# working.net
KiCad netlist of a schematic drawn in EAGLE
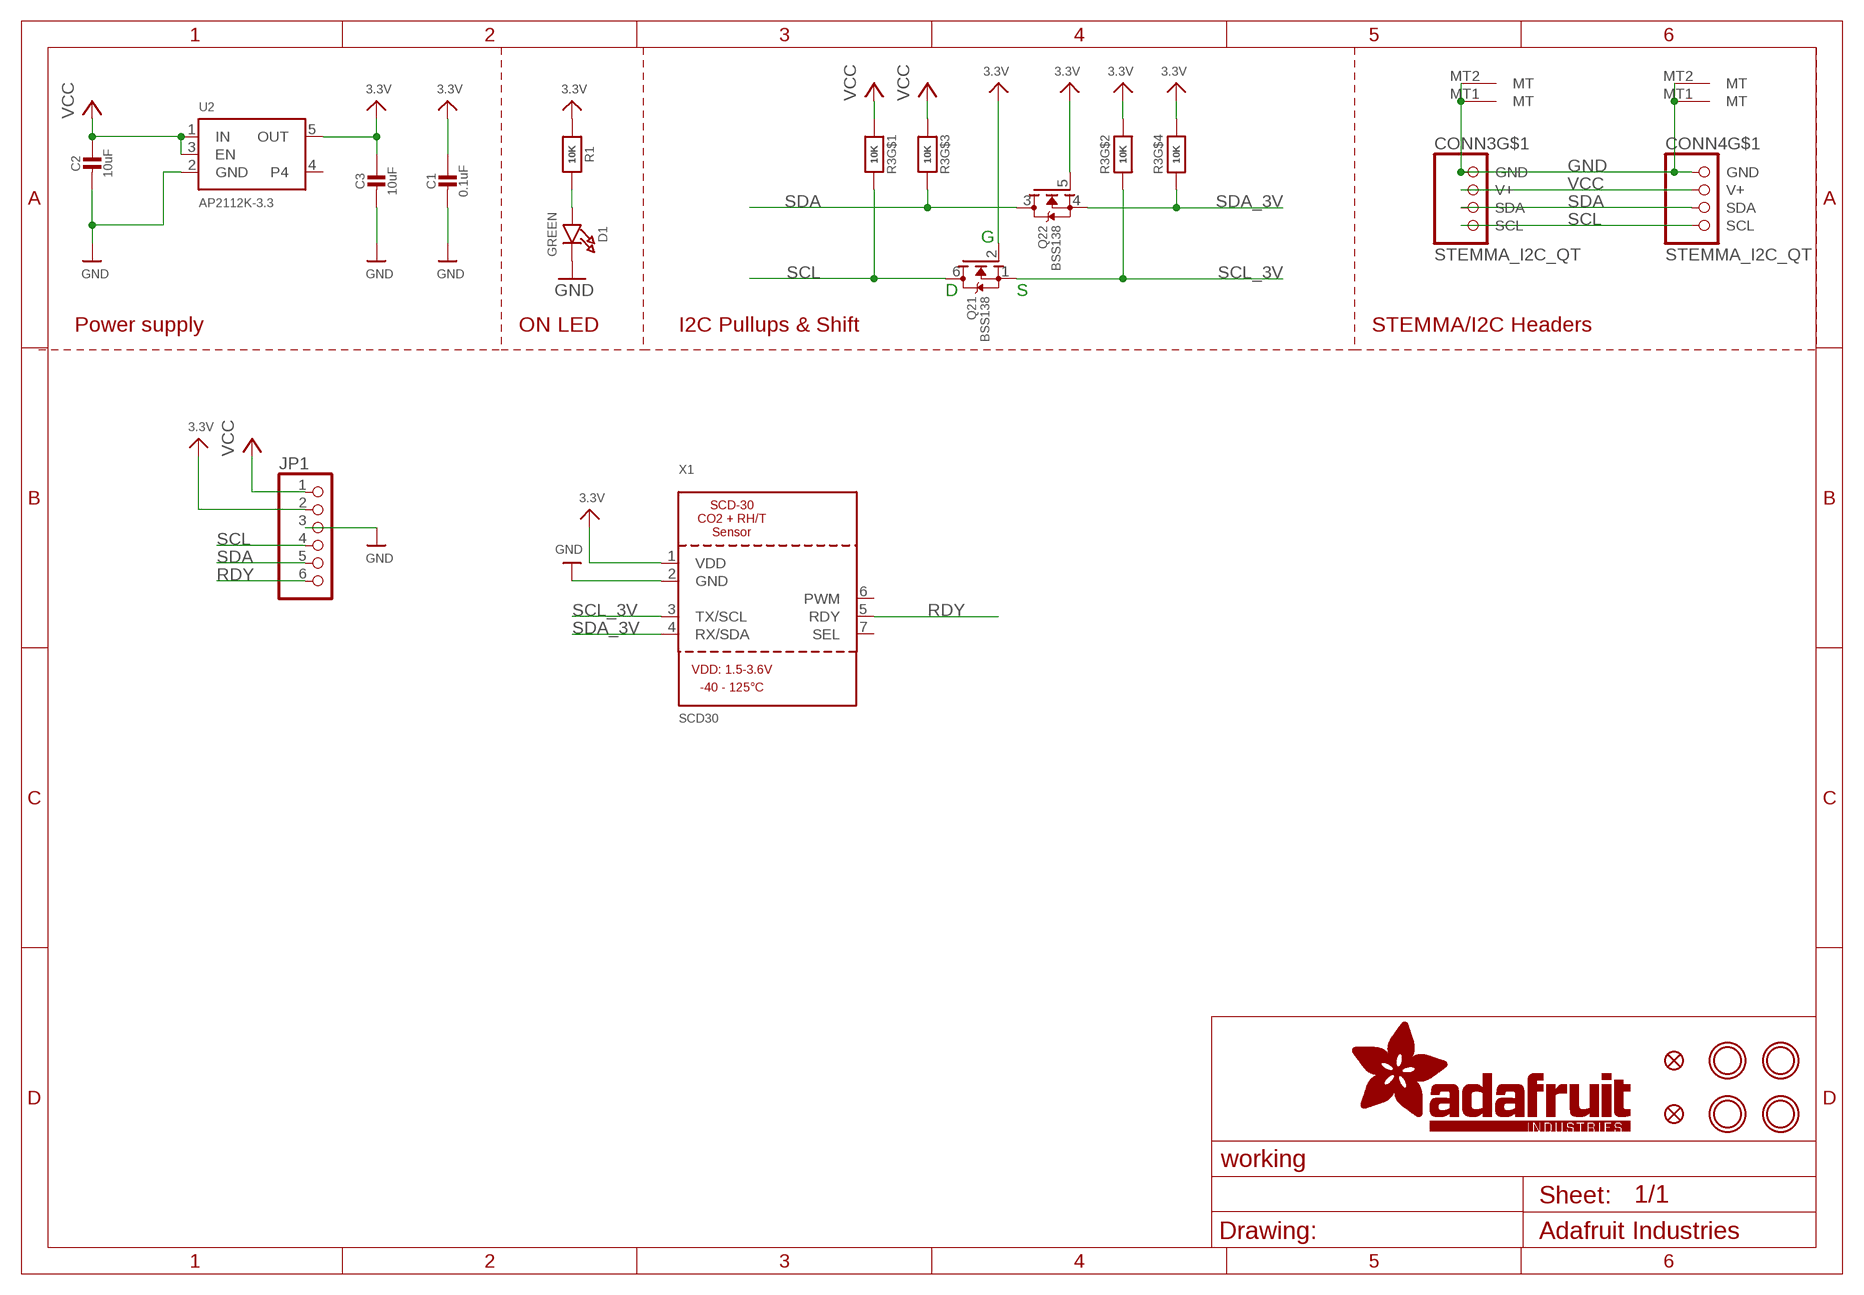
[diagram p0: schematic, sheet 1]

(export (version "E")
  (design (tool "Eeschema 10.0.6"))
  (components
    (comp (ref "C1")
      (value "0.1uF")
      (footprint "eagle-import:0603-NO")
      (libsource (lib "eagle-import") (part "CAP_CERAMIC0603_NO"))
    )
    (comp (ref "C2")
      (value "10uF")
      (footprint "eagle-import:0805-NO")
      (libsource (lib "eagle-import") (part "CAP_CERAMIC0805-NOOUTLINE"))
    )
    (comp (ref "C3")
      (value "10uF")
      (footprint "eagle-import:0805-NO")
      (libsource (lib "eagle-import") (part "CAP_CERAMIC0805-NOOUTLINE"))
    )
    (comp (ref "CONN3")
      (value "STEMMA_I2C_QT")
      (footprint "eagle-import:JST_SH4")
      (libsource (lib "eagle-import") (part "STEMMA_I2C_QT"))
    )
    (comp (ref "CONN4")
      (value "STEMMA_I2C_QT")
      (footprint "eagle-import:JST_SH4")
      (libsource (lib "eagle-import") (part "STEMMA_I2C_QT"))
    )
    (comp (ref "D1")
      (value "GREEN")
      (footprint "eagle-import:CHIPLED_0603_NOOUTLINE")
      (libsource (lib "eagle-import") (part "LED0603_NOOUTLINE"))
    )
    (comp (ref "FID3")
      (value "FIDUCIAL_1MM")
      (footprint "eagle-import:FIDUCIAL_1MM")
      (libsource (lib "eagle-import") (part "FIDUCIAL_1MM"))
    )
    (comp (ref "FID4")
      (value "FIDUCIAL_1MM")
      (footprint "eagle-import:FIDUCIAL_1MM")
      (libsource (lib "eagle-import") (part "FIDUCIAL_1MM"))
    )
    (comp (ref "JP1")
      (value "HEADER-1X670MIL")
      (footprint "eagle-import:1X06_ROUND_70")
      (libsource (lib "eagle-import") (part "HEADER-1X670MIL"))
    )
    (comp (ref "Q2")
      (value "BSS138")
      (footprint "eagle-import:SOT363")
      (libsource (lib "eagle-import") (part "MOSFET-N_DUAL"))
    )
    (comp (ref "R1")
      (value "10K")
      (footprint "eagle-import:0603-NO")
      (libsource (lib "eagle-import") (part "RESISTOR_0603_NOOUT"))
    )
    (comp (ref "R3")
      (value "10K")
      (footprint "eagle-import:RESPACK_4X0603")
      (libsource (lib "eagle-import") (part "RESISTOR_4PACK"))
    )
    (comp (ref "U$1")
      (value "MOUNTINGHOLE2.5")
      (footprint "eagle-import:MOUNTINGHOLE_2.5_PLATED")
      (libsource (lib "eagle-import") (part "MOUNTINGHOLE2.5"))
    )
    (comp (ref "U$17")
      (value "MOUNTINGHOLE2.5")
      (footprint "eagle-import:MOUNTINGHOLE_2.5_PLATED")
      (libsource (lib "eagle-import") (part "MOUNTINGHOLE2.5"))
    )
    (comp (ref "U$19")
      (value "MOUNTINGHOLE2.5")
      (footprint "eagle-import:MOUNTINGHOLE_2.5_PLATED")
      (libsource (lib "eagle-import") (part "MOUNTINGHOLE2.5"))
    )
    (comp (ref "U$21")
      (value "MOUNTINGHOLE2.5")
      (footprint "eagle-import:MOUNTINGHOLE_2.5_PLATED")
      (libsource (lib "eagle-import") (part "MOUNTINGHOLE2.5"))
    )
    (comp (ref "U2")
      (value "AP2112K-3.3")
      (footprint "eagle-import:SOT23-5")
      (libsource (lib "eagle-import") (part "VREG_SOT23-5"))
    )
    (comp (ref "X1")
      (value "SCD30")
      (footprint "eagle-import:SCD30")
      (libsource (lib "eagle-import") (part "SCD30"))
    )
  )
  (nets
    (net (code "1") (name "/RDY") (class "Default")
      (node (ref "JP1") (pin "6") (pinfunction "6_6") (pintype "passive"))
      (node (ref "X1") (pin "5") (pinfunction "RDY_5") (pintype "output"))
    )
    (net (code "2") (name "/SCL") (class "Default")
      (node (ref "CONN3") (pin "4") (pinfunction "SCL_4") (pintype "passive"))
      (node (ref "CONN4") (pin "4") (pinfunction "SCL_4") (pintype "passive"))
      (node (ref "JP1") (pin "4") (pinfunction "4_4") (pintype "passive"))
      (node (ref "Q2") (pin "6") (pinfunction "D_6") (pintype "bidirectional"))
      (node (ref "R3") (pin "8") (pinfunction "2_8") (pintype "passive"))
    )
    (net (code "3") (name "/SCL_3V") (class "Default")
      (node (ref "Q2") (pin "1") (pinfunction "S_1") (pintype "bidirectional"))
      (node (ref "R3") (pin "7") (pinfunction "2_7") (pintype "passive"))
      (node (ref "X1") (pin "3") (pinfunction "TX/SCL_3") (pintype "input"))
    )
    (net (code "4") (name "/SDA") (class "Default")
      (node (ref "CONN3") (pin "3") (pinfunction "SDA_3") (pintype "passive"))
      (node (ref "CONN4") (pin "3") (pinfunction "SDA_3") (pintype "passive"))
      (node (ref "JP1") (pin "5") (pinfunction "5_5") (pintype "passive"))
      (node (ref "Q2") (pin "3") (pinfunction "D_3") (pintype "bidirectional"))
      (node (ref "R3") (pin "6") (pinfunction "2_6") (pintype "passive"))
    )
    (net (code "5") (name "/SDA_3V") (class "Default")
      (node (ref "Q2") (pin "4") (pinfunction "S_4") (pintype "bidirectional"))
      (node (ref "R3") (pin "5") (pinfunction "2_5") (pintype "passive"))
      (node (ref "X1") (pin "4") (pinfunction "RX/SDA_4") (pintype "bidirectional"))
    )
    (net (code "6") (name "3.3V") (class "Default")
      (node (ref "C1") (pin "1") (pinfunction "1_1") (pintype "passive"))
      (node (ref "C3") (pin "1") (pinfunction "1_1") (pintype "passive"))
      (node (ref "JP1") (pin "2") (pinfunction "2_2") (pintype "passive"))
      (node (ref "Q2") (pin "2") (pinfunction "G_2") (pintype "bidirectional"))
      (node (ref "Q2") (pin "5") (pinfunction "G_5") (pintype "bidirectional"))
      (node (ref "R1") (pin "1") (pinfunction "1_1") (pintype "passive"))
      (node (ref "R3") (pin "2") (pinfunction "1_2") (pintype "passive"))
      (node (ref "R3") (pin "4") (pinfunction "1_4") (pintype "passive"))
      (node (ref "U2") (pin "5") (pinfunction "OUT_5") (pintype "power_in"))
      (node (ref "X1") (pin "1") (pinfunction "VDD_1") (pintype "power_in"))
    )
    (net (code "7") (name "GND") (class "Default")
      (node (ref "C1") (pin "2") (pinfunction "2_2") (pintype "passive"))
      (node (ref "C2") (pin "2") (pinfunction "2_2") (pintype "passive"))
      (node (ref "C3") (pin "2") (pinfunction "2_2") (pintype "passive"))
      (node (ref "CONN3") (pin "1") (pinfunction "GND_1") (pintype "passive"))
      (node (ref "CONN3") (pin "MT1") (pinfunction "MT_MT1") (pintype "bidirectional"))
      (node (ref "CONN3") (pin "MT2") (pinfunction "MT_MT2") (pintype "bidirectional"))
      (node (ref "CONN4") (pin "1") (pinfunction "GND_1") (pintype "passive"))
      (node (ref "CONN4") (pin "MT1") (pinfunction "MT_MT1") (pintype "bidirectional"))
      (node (ref "CONN4") (pin "MT2") (pinfunction "MT_MT2") (pintype "bidirectional"))
      (node (ref "D1") (pin "C") (pinfunction "C_C") (pintype "passive"))
      (node (ref "JP1") (pin "3") (pinfunction "3_3") (pintype "passive"))
      (node (ref "U2") (pin "2") (pinfunction "GND_2") (pintype "power_in"))
      (node (ref "X1") (pin "2") (pinfunction "GND_2") (pintype "power_in"))
    )
    (net (code "8") (name "Net-(D1-PadA)") (class "Default")
      (node (ref "D1") (pin "A") (pinfunction "A_A") (pintype "passive"))
      (node (ref "R1") (pin "2") (pinfunction "2_2") (pintype "passive"))
    )
    (net (code "9") (name "VCC") (class "Default")
      (node (ref "C2") (pin "1") (pinfunction "1_1") (pintype "passive"))
      (node (ref "CONN3") (pin "2") (pinfunction "V+_2") (pintype "passive"))
      (node (ref "CONN4") (pin "2") (pinfunction "V+_2") (pintype "passive"))
      (node (ref "JP1") (pin "1") (pinfunction "1_1") (pintype "passive"))
      (node (ref "R3") (pin "1") (pinfunction "1_1") (pintype "passive"))
      (node (ref "R3") (pin "3") (pinfunction "1_3") (pintype "passive"))
      (node (ref "U2") (pin "1") (pinfunction "IN_1") (pintype "power_in"))
      (node (ref "U2") (pin "3") (pinfunction "EN_3") (pintype "input"))
    )
    (net (code "10") (name "unconnected-(U2-P4-Pad4)") (class "Default")
      (node (ref "U2") (pin "4") (pinfunction "P4_4") (pintype "bidirectional"))
    )
    (net (code "11") (name "unconnected-(X1-PWM-Pad6)") (class "Default")
      (node (ref "X1") (pin "6") (pinfunction "PWM_6") (pintype "output"))
    )
    (net (code "12") (name "unconnected-(X1-SEL-Pad7)") (class "Default")
      (node (ref "X1") (pin "7") (pinfunction "SEL_7") (pintype "input"))
    )
  )
)
